# Sheet1.net
KiCad netlist of a schematic drawn in Altium Designer
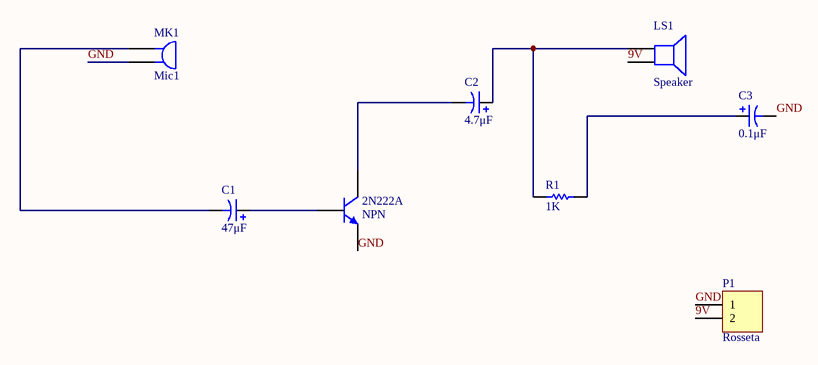
[diagram p0: Sheet1.SchDoc]

(export (version "E")
  (design (tool "Eeschema 10.0.6"))
  (components
    (comp (ref "2N222A")
      (value "NPN")
      (footprint "TO-226-AA")
      (description "NPN Bipolar Transistor")
      (fields (field (name "PUBLISHER") "Altium Limited"))
      (libsource (lib "Miscellaneous Devices") (part "NPN"))
    )
    (comp (ref "C1")
      (value "47μF")
      (footprint "RB7.6-15")
      (description "Polarized Capacitor (Radial)")
      (fields (field (name "PUBLISHER") "Altium Limited"))
      (libsource (lib "Miscellaneous Devices") (part "Cap Pol1"))
    )
    (comp (ref "C2")
      (value "4.7μF")
      (footprint "RB7.6-15")
      (description "Polarized Capacitor (Radial)")
      (fields (field (name "PUBLISHER") "Altium Limited"))
      (libsource (lib "Miscellaneous Devices") (part "Cap Pol1"))
    )
    (comp (ref "C3")
      (value "0.1μF")
      (footprint "RB7.6-15")
      (description "Polarized Capacitor (Radial)")
      (fields (field (name "PUBLISHER") "Altium Limited"))
      (libsource (lib "Miscellaneous Devices") (part "Cap Pol1"))
    )
    (comp (ref "LS1")
      (value "Speaker")
      (footprint "PIN2")
      (description "Loudspeaker")
      (fields (field (name "PUBLISHER") "Altium Limited"))
      (libsource (lib "Miscellaneous Devices") (part "Speaker"))
    )
    (comp (ref "MK1")
      (value "Mic1")
      (footprint "PIN2")
      (description "Microphone")
      (fields (field (name "PUBLISHER") "Altium Limited"))
      (libsource (lib "Miscellaneous Devices") (part "Mic1"))
    )
    (comp (ref "P1")
      (value "Rosseta")
      (footprint "HDR1X2")
      (description "Header, 2-Pin")
      (fields (field (name "PUBLISHER") "Altium Limited"))
      (libsource (lib "Miscellaneous Connectors") (part "Header 2"))
    )
    (comp (ref "R1")
      (value "1K")
      (footprint "AXIAL-0.3")
      (description "Resistor")
      (fields (field (name "PUBLISHER") "Altium Limited"))
      (libsource (lib "Miscellaneous Devices") (part "Res1"))
    )
  )
  (nets
    (net (code "1") (name "/9V") (class "Default")
      (node (ref "LS1") (pin "2") (pinfunction "2_2") (pintype "passive"))
      (node (ref "P1") (pin "2") (pinfunction "2_2") (pintype "passive"))
    )
    (net (code "2") (name "/GND") (class "Default")
      (node (ref "2N222A") (pin "3") (pinfunction "E_3") (pintype "passive"))
      (node (ref "C3") (pin "2") (pinfunction "2_2") (pintype "passive"))
      (node (ref "MK1") (pin "2") (pinfunction "2_2") (pintype "passive"))
      (node (ref "P1") (pin "1") (pinfunction "1_1") (pintype "passive"))
    )
    (net (code "3") (name "Net-(2N222A-B)") (class "Default")
      (node (ref "2N222A") (pin "2") (pinfunction "B_2") (pintype "passive"))
      (node (ref "C1") (pin "1") (pinfunction "1_1") (pintype "passive"))
    )
    (net (code "4") (name "Net-(2N222A-C)") (class "Default")
      (node (ref "2N222A") (pin "1") (pinfunction "C_1") (pintype "passive"))
      (node (ref "C2") (pin "2") (pinfunction "2_2") (pintype "passive"))
    )
    (net (code "5") (name "Net-(C1-Pad2)") (class "Default")
      (node (ref "C1") (pin "2") (pinfunction "2_2") (pintype "passive"))
      (node (ref "MK1") (pin "1") (pinfunction "1_1") (pintype "passive"))
    )
    (net (code "6") (name "Net-(C2-Pad1)") (class "Default")
      (node (ref "C2") (pin "1") (pinfunction "1_1") (pintype "passive"))
      (node (ref "LS1") (pin "1") (pinfunction "1_1") (pintype "passive"))
      (node (ref "R1") (pin "1") (pinfunction "1_1") (pintype "passive"))
    )
    (net (code "7") (name "Net-(C3-Pad1)") (class "Default")
      (node (ref "C3") (pin "1") (pinfunction "1_1") (pintype "passive"))
      (node (ref "R1") (pin "2") (pinfunction "2_2") (pintype "passive"))
    )
  )
)
